# RTM_4SFP_3QSFP_TOP.net
KiCad netlist of a schematic drawn in Altium Designer
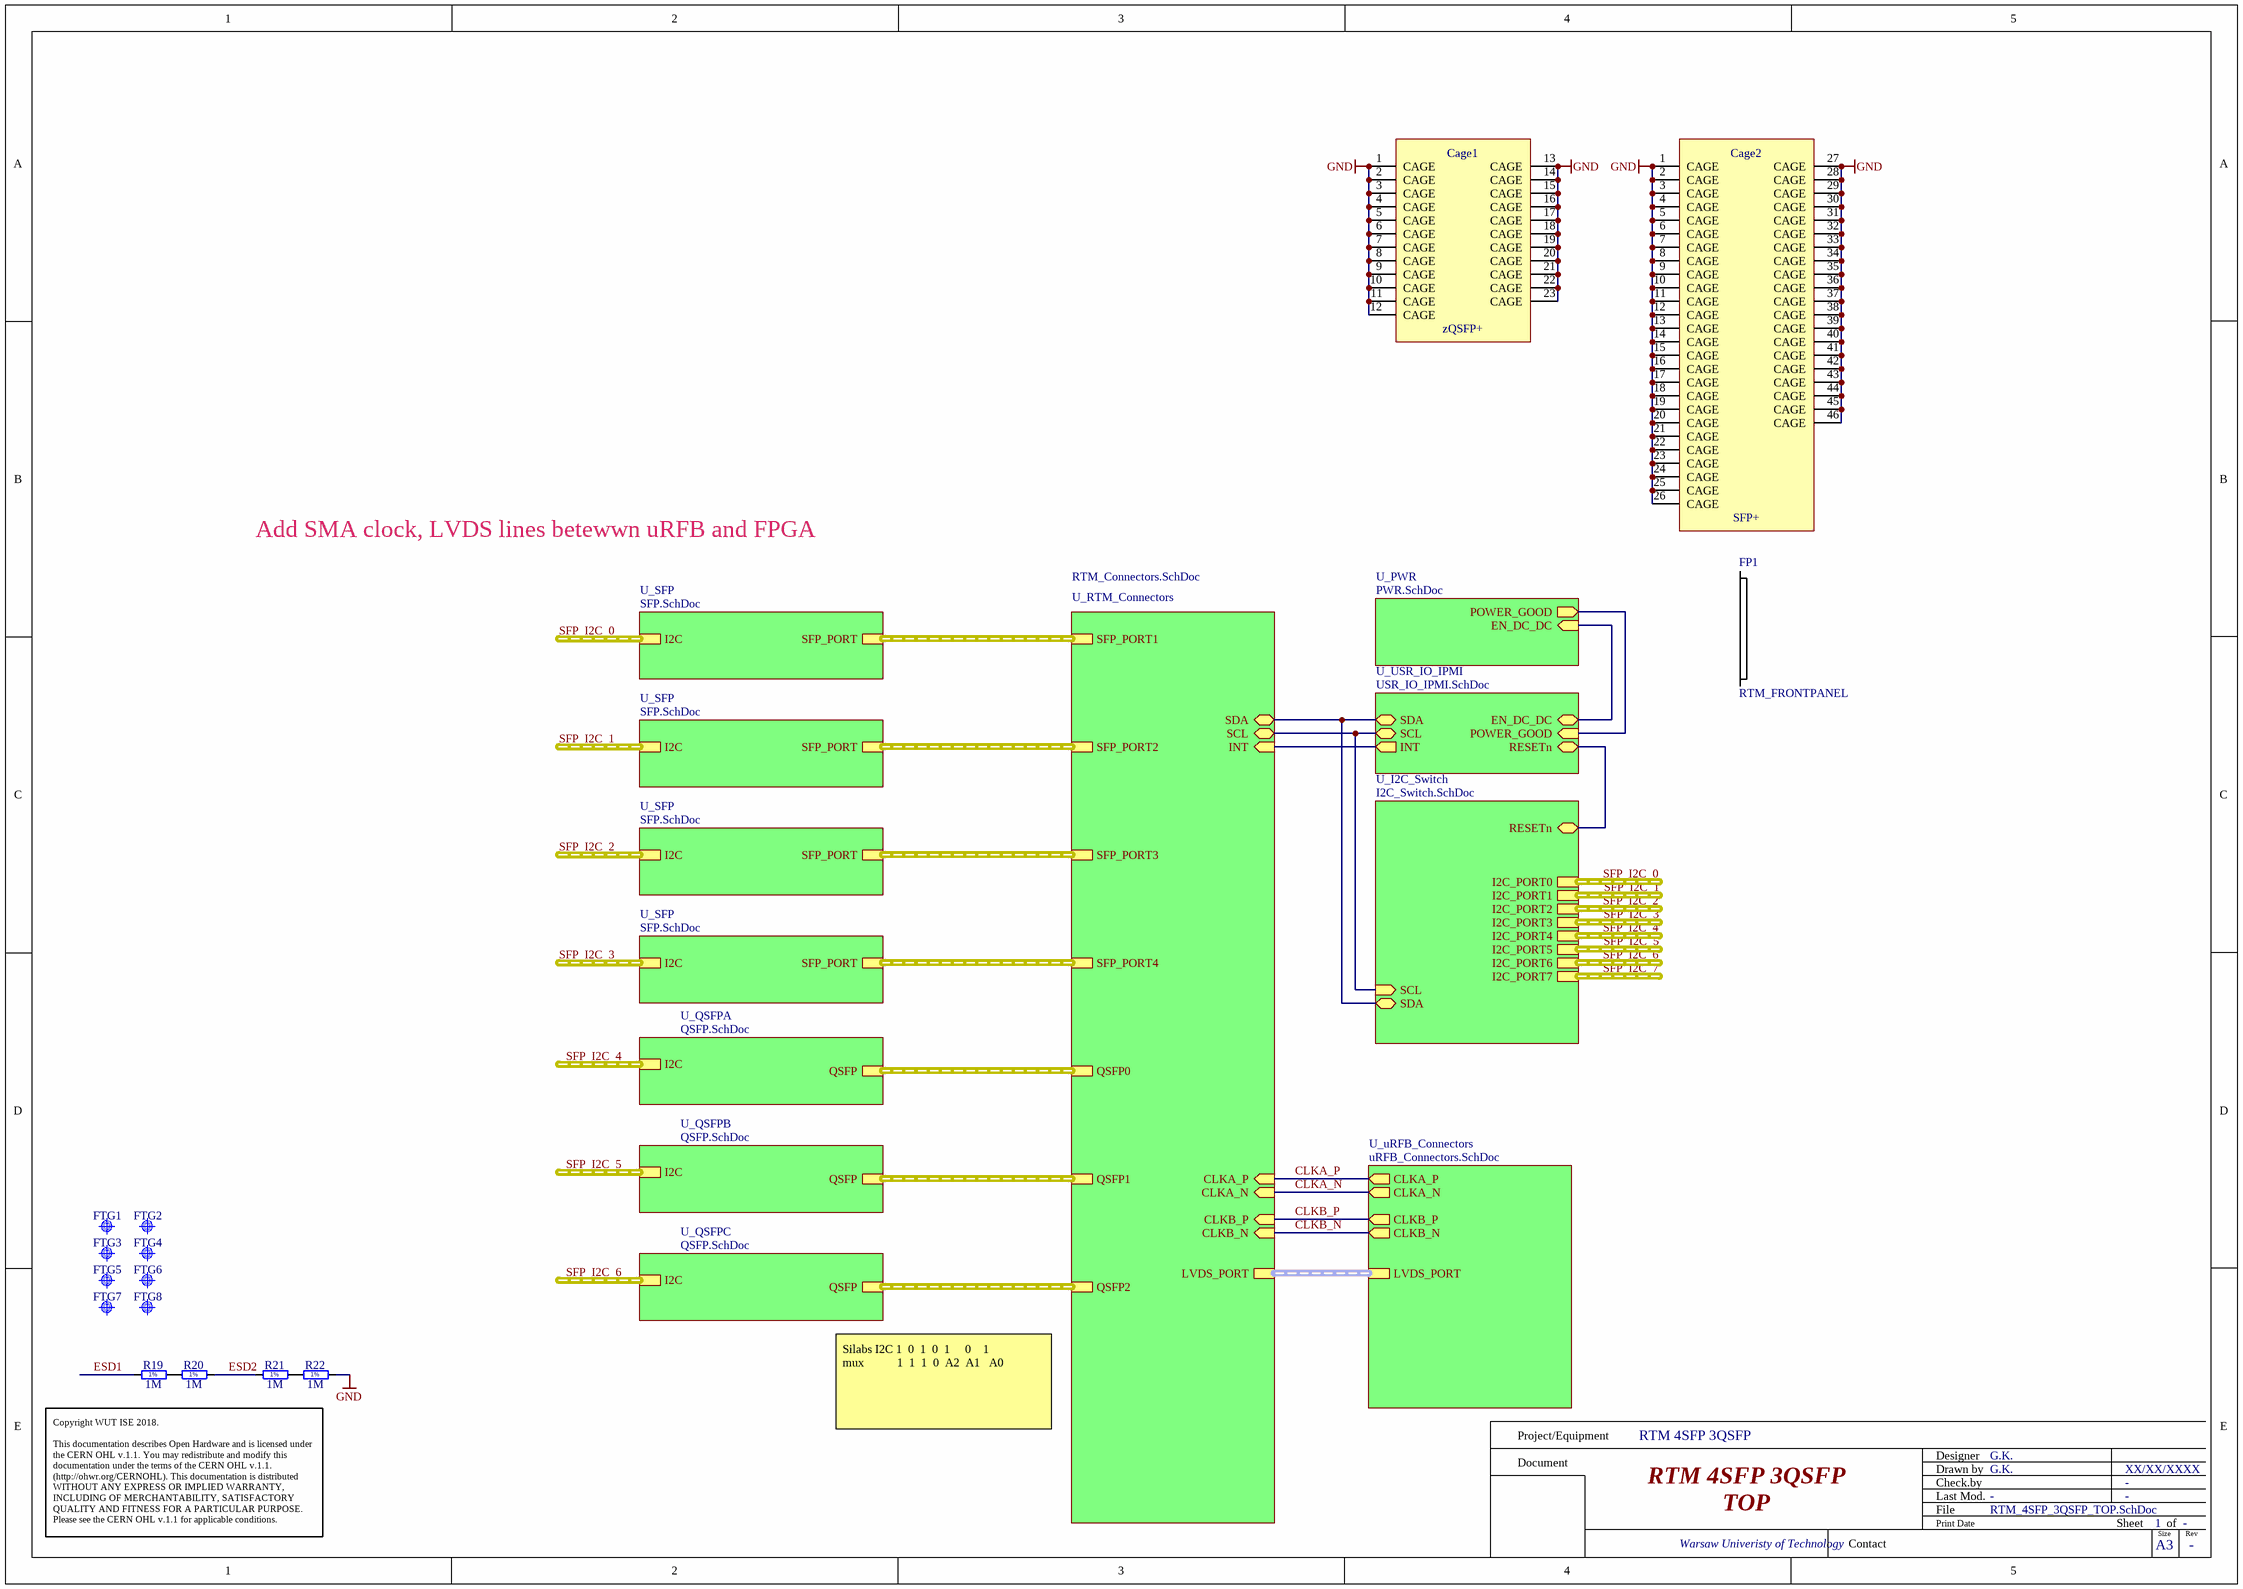
[diagram p0: RTM_4SFP_3QSFP_TOP.SchDoc]

(export (version "E")
  (design (tool "Eeschema 10.0.6"))
  (components
    (comp (ref "Cage1")
      (value "zQSFP+")
      (footprint "TYCO_2170737-1")
      (description "QSFP+ 1x3 Cage (23Pins)")
      (fields
        (field (name "PART NUMBER") "TYCO_2170737-1")
        (field (name "MANUFACTURER") "TYCO ELECTRONICS")
        (field (name "AUTHOR") "CERN DEM JLC")
      )
      (libsource (lib "Connectors") (part "QSFP+ 1x3 Cage (23Pins)"))
    )
    (comp (ref "Cage2")
      (value "SFP+")
      (footprint "TYCO_2007132-1")
      (description "SFP+  1x4 Cage (46 Pins)")
      (fields
        (field (name "PART NUMBER") "TYCO_2007132-1")
        (field (name "MANUFACTURER") "TYCO ELECTRONICS")
        (field (name "AUTHOR") "CERN DEM JLC")
      )
      (libsource (lib "Connectors") (part "SFP+ 1x4 Cage (46Pins)"))
    )
    (comp (ref "FP1")
      (value "RTM_FRONTPANEL")
      (footprint "RTM_FRONTPANEL")
      (description "RTM Frontpanel")
      (libsource (lib "SchematicComponents") (part "RTM_FRONTPANEL"))
    )
    (comp (ref "FTG1")
      (value "Use only in PCB")
      (footprint "FIDUCIAL_TOP_S100-200")
      (description "Fiducial Target")
      (fields (field (name "PART NUMBER") "FIDUCIAL_TARGET_S100-200") (field (name "AUTHOR") "CERN DEM JLC"))
      (libsource (lib "Eletro-mechanical") (part "Fiducial Target"))
    )
    (comp (ref "FTG2")
      (value "Use only in PCB")
      (footprint "FIDUCIAL_TOP_S100-200")
      (description "Fiducial Target")
      (fields (field (name "PART NUMBER") "FIDUCIAL_TARGET_S100-200") (field (name "AUTHOR") "CERN DEM JLC"))
      (libsource (lib "Eletro-mechanical") (part "Fiducial Target"))
    )
    (comp (ref "FTG3")
      (value "Use only in PCB")
      (footprint "FIDUCIAL_TOP_S100-200")
      (description "Fiducial Target")
      (fields (field (name "PART NUMBER") "FIDUCIAL_TARGET_S100-200") (field (name "AUTHOR") "CERN DEM JLC"))
      (libsource (lib "Eletro-mechanical") (part "Fiducial Target"))
    )
    (comp (ref "FTG4")
      (value "Use only in PCB")
      (footprint "FIDUCIAL_TOP_S100-200")
      (description "Fiducial Target")
      (fields (field (name "PART NUMBER") "FIDUCIAL_TARGET_S100-200") (field (name "AUTHOR") "CERN DEM JLC"))
      (libsource (lib "Eletro-mechanical") (part "Fiducial Target"))
    )
    (comp (ref "FTG5")
      (value "Use only in PCB")
      (footprint "FIDUCIAL_TOP_S100-200")
      (description "Fiducial Target")
      (fields (field (name "PART NUMBER") "FIDUCIAL_TARGET_S100-200") (field (name "AUTHOR") "CERN DEM JLC"))
      (libsource (lib "Eletro-mechanical") (part "Fiducial Target"))
    )
    (comp (ref "FTG6")
      (value "Use only in PCB")
      (footprint "FIDUCIAL_TOP_S100-200")
      (description "Fiducial Target")
      (fields (field (name "PART NUMBER") "FIDUCIAL_TARGET_S100-200") (field (name "AUTHOR") "CERN DEM JLC"))
      (libsource (lib "Eletro-mechanical") (part "Fiducial Target"))
    )
    (comp (ref "FTG7")
      (value "Use only in PCB")
      (footprint "FIDUCIAL_TOP_S100-200")
      (description "Fiducial Target")
      (fields (field (name "PART NUMBER") "FIDUCIAL_TARGET_S100-200") (field (name "AUTHOR") "CERN DEM JLC"))
      (libsource (lib "Eletro-mechanical") (part "Fiducial Target"))
    )
    (comp (ref "FTG8")
      (value "Use only in PCB")
      (footprint "FIDUCIAL_TOP_S100-200")
      (description "Fiducial Target")
      (fields (field (name "PART NUMBER") "FIDUCIAL_TARGET_S100-200") (field (name "AUTHOR") "CERN DEM JLC"))
      (libsource (lib "Eletro-mechanical") (part "Fiducial Target"))
    )
    (comp (ref "R19")
      (value "1M")
      (footprint "RESC3216X65N")
      (description "Resistor - 1%")
      (fields
        (field (name "PART NUMBER") "R1206_1M_1%_0.25W_100PPM")
        (field (name "POWER") "0.25W")
        (field (name "AUTHOR") "CERN DEM JLC")
      )
      (libsource (lib "Resistors") (part "Resistor - 1%"))
    )
    (comp (ref "R20")
      (value "1M")
      (footprint "RESC3216X65N")
      (description "Resistor - 1%")
      (fields
        (field (name "PART NUMBER") "R1206_1M_1%_0.25W_100PPM")
        (field (name "POWER") "0.25W")
        (field (name "AUTHOR") "CERN DEM JLC")
      )
      (libsource (lib "Resistors") (part "Resistor - 1%"))
    )
    (comp (ref "R21")
      (value "1M")
      (footprint "RESC3216X65N")
      (description "Resistor - 1%")
      (fields
        (field (name "PART NUMBER") "R1206_1M_1%_0.25W_100PPM")
        (field (name "POWER") "0.25W")
        (field (name "AUTHOR") "CERN DEM JLC")
      )
      (libsource (lib "Resistors") (part "Resistor - 1%"))
    )
    (comp (ref "R22")
      (value "1M")
      (footprint "RESC3216X65N")
      (description "Resistor - 1%")
      (fields
        (field (name "PART NUMBER") "R1206_1M_1%_0.25W_100PPM")
        (field (name "POWER") "0.25W")
        (field (name "AUTHOR") "CERN DEM JLC")
      )
      (libsource (lib "Resistors") (part "Resistor - 1%"))
    )
  )
  (nets
    (net (code "14") (name "/ESD1") (class "Default")
      (node (ref "R19") (pin "1") (pinfunction "1_1") (pintype "passive"))
    )
    (net (code "15") (name "/ESD2") (class "Default")
      (node (ref "R20") (pin "2") (pinfunction "2_2") (pintype "passive"))
      (node (ref "R21") (pin "1") (pinfunction "1_1") (pintype "passive"))
    )
    (net (code "37") (name "GND") (class "Default")
      (node (ref "Cage1") (pin "1") (pinfunction "CAGE_1") (pintype "power_in"))
      (node (ref "Cage1") (pin "10") (pinfunction "CAGE_10") (pintype "power_in"))
      (node (ref "Cage1") (pin "11") (pinfunction "CAGE_11") (pintype "power_in"))
      (node (ref "Cage1") (pin "12") (pinfunction "CAGE_12") (pintype "power_in"))
      (node (ref "Cage1") (pin "13") (pinfunction "CAGE_13") (pintype "power_in"))
      (node (ref "Cage1") (pin "14") (pinfunction "CAGE_14") (pintype "power_in"))
      (node (ref "Cage1") (pin "15") (pinfunction "CAGE_15") (pintype "power_in"))
      (node (ref "Cage1") (pin "16") (pinfunction "CAGE_16") (pintype "power_in"))
      (node (ref "Cage1") (pin "17") (pinfunction "CAGE_17") (pintype "power_in"))
      (node (ref "Cage1") (pin "18") (pinfunction "CAGE_18") (pintype "power_in"))
      (node (ref "Cage1") (pin "19") (pinfunction "CAGE_19") (pintype "power_in"))
      (node (ref "Cage1") (pin "2") (pinfunction "CAGE_2") (pintype "power_in"))
      (node (ref "Cage1") (pin "20") (pinfunction "CAGE_20") (pintype "power_in"))
      (node (ref "Cage1") (pin "21") (pinfunction "CAGE_21") (pintype "power_in"))
      (node (ref "Cage1") (pin "22") (pinfunction "CAGE_22") (pintype "power_in"))
      (node (ref "Cage1") (pin "23") (pinfunction "CAGE_23") (pintype "power_in"))
      (node (ref "Cage1") (pin "3") (pinfunction "CAGE_3") (pintype "power_in"))
      (node (ref "Cage1") (pin "4") (pinfunction "CAGE_4") (pintype "power_in"))
      (node (ref "Cage1") (pin "5") (pinfunction "CAGE_5") (pintype "power_in"))
      (node (ref "Cage1") (pin "6") (pinfunction "CAGE_6") (pintype "power_in"))
      (node (ref "Cage1") (pin "7") (pinfunction "CAGE_7") (pintype "power_in"))
      (node (ref "Cage1") (pin "8") (pinfunction "CAGE_8") (pintype "power_in"))
      (node (ref "Cage1") (pin "9") (pinfunction "CAGE_9") (pintype "power_in"))
      (node (ref "Cage2") (pin "1") (pinfunction "CAGE_1") (pintype "power_in"))
      (node (ref "Cage2") (pin "10") (pinfunction "CAGE_10") (pintype "power_in"))
      (node (ref "Cage2") (pin "11") (pinfunction "CAGE_11") (pintype "power_in"))
      (node (ref "Cage2") (pin "12") (pinfunction "CAGE_12") (pintype "power_in"))
      (node (ref "Cage2") (pin "13") (pinfunction "CAGE_13") (pintype "power_in"))
      (node (ref "Cage2") (pin "14") (pinfunction "CAGE_14") (pintype "power_in"))
      (node (ref "Cage2") (pin "15") (pinfunction "CAGE_15") (pintype "power_in"))
      (node (ref "Cage2") (pin "16") (pinfunction "CAGE_16") (pintype "power_in"))
      (node (ref "Cage2") (pin "17") (pinfunction "CAGE_17") (pintype "power_in"))
      (node (ref "Cage2") (pin "18") (pinfunction "CAGE_18") (pintype "power_in"))
      (node (ref "Cage2") (pin "19") (pinfunction "CAGE_19") (pintype "power_in"))
      (node (ref "Cage2") (pin "2") (pinfunction "CAGE_2") (pintype "power_in"))
      (node (ref "Cage2") (pin "20") (pinfunction "CAGE_20") (pintype "power_in"))
      (node (ref "Cage2") (pin "21") (pinfunction "CAGE_21") (pintype "power_in"))
      (node (ref "Cage2") (pin "22") (pinfunction "CAGE_22") (pintype "power_in"))
      (node (ref "Cage2") (pin "23") (pinfunction "CAGE_23") (pintype "power_in"))
      (node (ref "Cage2") (pin "24") (pinfunction "CAGE_24") (pintype "power_in"))
      (node (ref "Cage2") (pin "25") (pinfunction "CAGE_25") (pintype "power_in"))
      (node (ref "Cage2") (pin "26") (pinfunction "CAGE_26") (pintype "power_in"))
      (node (ref "Cage2") (pin "27") (pinfunction "CAGE_27") (pintype "power_in"))
      (node (ref "Cage2") (pin "28") (pinfunction "CAGE_28") (pintype "power_in"))
      (node (ref "Cage2") (pin "29") (pinfunction "CAGE_29") (pintype "power_in"))
      (node (ref "Cage2") (pin "3") (pinfunction "CAGE_3") (pintype "power_in"))
      (node (ref "Cage2") (pin "30") (pinfunction "CAGE_30") (pintype "power_in"))
      (node (ref "Cage2") (pin "31") (pinfunction "CAGE_31") (pintype "power_in"))
      (node (ref "Cage2") (pin "32") (pinfunction "CAGE_32") (pintype "power_in"))
      (node (ref "Cage2") (pin "33") (pinfunction "CAGE_33") (pintype "power_in"))
      (node (ref "Cage2") (pin "34") (pinfunction "CAGE_34") (pintype "power_in"))
      (node (ref "Cage2") (pin "35") (pinfunction "CAGE_35") (pintype "power_in"))
      (node (ref "Cage2") (pin "36") (pinfunction "CAGE_36") (pintype "power_in"))
      (node (ref "Cage2") (pin "37") (pinfunction "CAGE_37") (pintype "power_in"))
      (node (ref "Cage2") (pin "38") (pinfunction "CAGE_38") (pintype "power_in"))
      (node (ref "Cage2") (pin "39") (pinfunction "CAGE_39") (pintype "power_in"))
      (node (ref "Cage2") (pin "4") (pinfunction "CAGE_4") (pintype "power_in"))
      (node (ref "Cage2") (pin "40") (pinfunction "CAGE_40") (pintype "power_in"))
      (node (ref "Cage2") (pin "41") (pinfunction "CAGE_41") (pintype "power_in"))
      (node (ref "Cage2") (pin "42") (pinfunction "CAGE_42") (pintype "power_in"))
      (node (ref "Cage2") (pin "43") (pinfunction "CAGE_43") (pintype "power_in"))
      (node (ref "Cage2") (pin "44") (pinfunction "CAGE_44") (pintype "power_in"))
      (node (ref "Cage2") (pin "45") (pinfunction "CAGE_45") (pintype "power_in"))
      (node (ref "Cage2") (pin "46") (pinfunction "CAGE_46") (pintype "power_in"))
      (node (ref "Cage2") (pin "5") (pinfunction "CAGE_5") (pintype "power_in"))
      (node (ref "Cage2") (pin "6") (pinfunction "CAGE_6") (pintype "power_in"))
      (node (ref "Cage2") (pin "7") (pinfunction "CAGE_7") (pintype "power_in"))
      (node (ref "Cage2") (pin "8") (pinfunction "CAGE_8") (pintype "power_in"))
      (node (ref "Cage2") (pin "9") (pinfunction "CAGE_9") (pintype "power_in"))
      (node (ref "R22") (pin "2") (pinfunction "2_2") (pintype "passive"))
    )
    (net (code "38") (name "Net-(R19-Pad2)") (class "Default")
      (node (ref "R19") (pin "2") (pinfunction "2_2") (pintype "passive"))
      (node (ref "R20") (pin "1") (pinfunction "1_1") (pintype "passive"))
    )
    (net (code "39") (name "Net-(R21-Pad2)") (class "Default")
      (node (ref "R21") (pin "2") (pinfunction "2_2") (pintype "passive"))
      (node (ref "R22") (pin "1") (pinfunction "1_1") (pintype "passive"))
    )
  )
)
